# led_driver.net
KiCad netlist of a schematic drawn in EAGLE
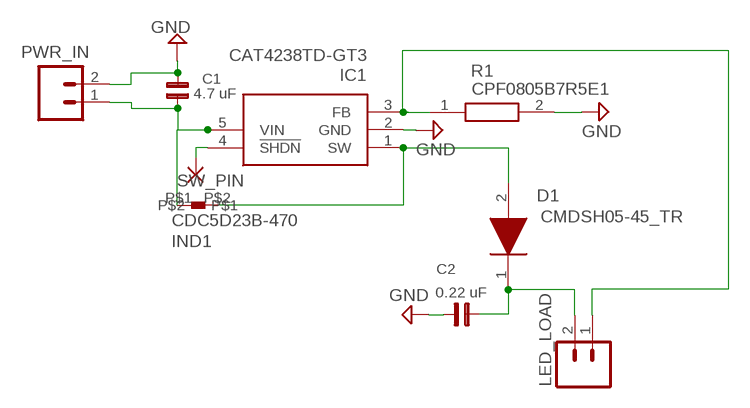
[diagram p0: schematic, sheet 1]

(export (version "E")
  (design (tool "Eeschema 10.0.6"))
  (components
    (comp (ref "C1")
      (value "4.7 uF")
      (footprint "eagle-import:0805")
      (libsource (lib "eagle-import") (part "C0805"))
    )
    (comp (ref "C2")
      (value "0.22 uF")
      (footprint "eagle-import:0805")
      (libsource (lib "eagle-import") (part "C0805"))
    )
    (comp (ref "D1")
      (value "CMDSH05-45_TR")
      (footprint "eagle-import:SOD2512X110N")
      (fields
        (field (name "MANUFACTURER_PART_NUMBER") "CMDSH05-45 TR")
        (field (name "MOUSER_PART_NUMBER") "610-CMDSH05-45TR")
      )
      (libsource (lib "eagle-import") (part "CMDSH05-45_TR"))
    )
    (comp (ref "IC1")
      (value "CAT4238TD-GT3")
      (footprint "eagle-import:SOT95P280X100-5N")
      (fields (field (name "MOUSER_PART_NUMBER") "698-CAT4238TDG"))
      (libsource (lib "eagle-import") (part "CAT4238TD-GT3"))
    )
    (comp (ref "IND1")
      (value "CDC5D23B-470")
      (footprint "eagle-import:CDC5D23B-470")
      (libsource (lib "eagle-import") (part "CDC5D23B-470"))
    )
    (comp (ref "LED_LOAD")
      (value "M02")
      (footprint "eagle-import:02P")
      (libsource (lib "eagle-import") (part "M02"))
    )
    (comp (ref "PWR_IN")
      (value "M02")
      (footprint "eagle-import:02P")
      (libsource (lib "eagle-import") (part "M02"))
    )
    (comp (ref "R1")
      (value "CPF0805B7R5E1")
      (footprint "eagle-import:RESC2012X65N")
      (fields (field (name "MOUSER_PART_NUMBER") "279-CPF0805B7R5E1"))
      (libsource (lib "eagle-import") (part "CPF0805B7R5E1"))
    )
    (comp (ref "SW_PIN")
      (value "2,54/1,1")
      (footprint "eagle-import:2,54_1,1")
      (libsource (lib "eagle-import") (part "2,54/1,1"))
    )
  )
  (nets
    (net (code "1") (name "GND") (class "Default")
      (node (ref "C1") (pin "2") (pinfunction "2_2") (pintype "passive"))
      (node (ref "C2") (pin "2") (pinfunction "2_2") (pintype "passive"))
      (node (ref "IC1") (pin "2") (pinfunction "GND_2") (pintype "power_in"))
      (node (ref "PWR_IN") (pin "2") (pinfunction "2_2") (pintype "passive"))
      (node (ref "R1") (pin "2") (pinfunction "2_2") (pintype "bidirectional"))
    )
    (net (code "2") (name "Net-(D1-A)") (class "Default")
      (node (ref "D1") (pin "2") (pinfunction "A_2") (pintype "bidirectional"))
      (node (ref "IC1") (pin "1") (pinfunction "SW_1") (pintype "bidirectional"))
      (node (ref "IND1") (pin "P$2") (pinfunction "P$2_P$2") (pintype "bidirectional"))
    )
    (net (code "3") (name "Net-(D1-K)") (class "Default")
      (node (ref "C2") (pin "1") (pinfunction "1_1") (pintype "passive"))
      (node (ref "D1") (pin "1") (pinfunction "K_1") (pintype "bidirectional"))
      (node (ref "LED_LOAD") (pin "2") (pinfunction "2_2") (pintype "passive"))
    )
    (net (code "4") (name "Net-(IC1-FB)") (class "Default")
      (node (ref "IC1") (pin "3") (pinfunction "FB_3") (pintype "bidirectional"))
      (node (ref "LED_LOAD") (pin "1") (pinfunction "1_1") (pintype "passive"))
      (node (ref "R1") (pin "1") (pinfunction "1_1") (pintype "bidirectional"))
    )
    (net (code "5") (name "Net-(IC1-VIN)") (class "Default")
      (node (ref "C1") (pin "1") (pinfunction "1_1") (pintype "passive"))
      (node (ref "IC1") (pin "5") (pinfunction "VIN_5") (pintype "input"))
      (node (ref "IND1") (pin "P$1") (pinfunction "P$1_P$1") (pintype "bidirectional"))
      (node (ref "PWR_IN") (pin "1") (pinfunction "1_1") (pintype "passive"))
    )
    (net (code "6") (name "Net-(IC1-~{SHDN})") (class "Default")
      (node (ref "IC1") (pin "4") (pinfunction "~{SHDN}_4") (pintype "bidirectional"))
      (node (ref "SW_PIN") (pin "1") (pinfunction "P_1") (pintype "passive"))
    )
  )
)
